# Truss-Power.net
KiCad netlist of a schematic drawn in EAGLE
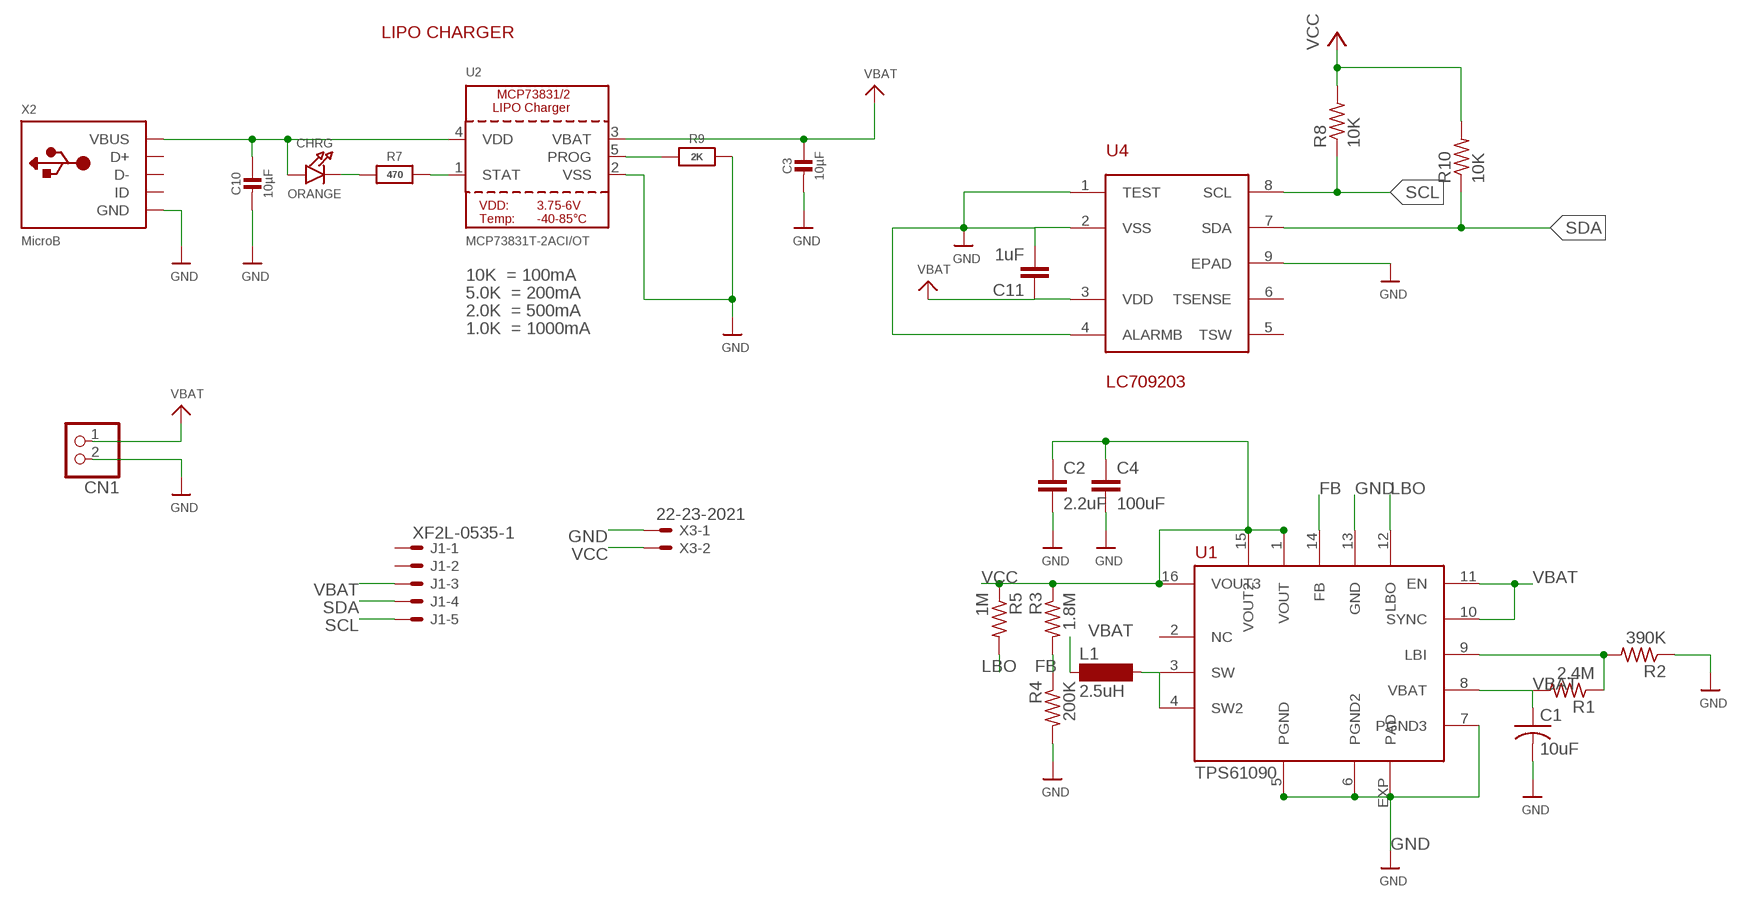
[diagram p0: schematic, sheet 1]

(export (version "E")
  (design (tool "Eeschema 10.0.6"))
  (components
    (comp (ref "C1")
      (value "10uF")
      (footprint "eagle-import:C0805K")
      (libsource (lib "eagle-import") (part "C-USC0805K"))
    )
    (comp (ref "C2")
      (value "2.2uF")
      (footprint "eagle-import:C0805K")
      (libsource (lib "eagle-import") (part "C-EUC0805K"))
    )
    (comp (ref "C3")
      (value "10µF")
      (footprint "eagle-import:0805-NO")
      (libsource (lib "eagle-import") (part "CAP_CERAMIC0805-NOOUTLINE"))
    )
    (comp (ref "C4")
      (value "100uF")
      (footprint "eagle-import:7343-METRIC")
      (libsource (lib "eagle-import") (part "TANT-CAP"))
    )
    (comp (ref "C10")
      (value "10µF")
      (footprint "eagle-import:0805-NO")
      (libsource (lib "eagle-import") (part "CAP_CERAMIC0805-NOOUTLINE"))
    )
    (comp (ref "C11")
      (value "1uF")
      (footprint "eagle-import:C0603")
      (libsource (lib "eagle-import") (part "C-EUC0603"))
    )
    (comp (ref "CHRG")
      (value "ORANGE")
      (footprint "eagle-import:CHIPLED_0805_NOOUTLINE")
      (libsource (lib "eagle-import") (part "LED0805_NOOUTLINE"))
    )
    (comp (ref "CN1")
      (value "JST_2PIN-SMT-RA")
      (footprint "eagle-import:JST-PH-2-SMT-RA")
      (libsource (lib "eagle-import") (part "JST_2PIN-SMT-RA"))
    )
    (comp (ref "J1")
      (value "XF2L-0535-1")
      (footprint "eagle-import:XF2L-0535-1")
      (fields (field (name "MPN") "XF2L-0535-1A"))
      (libsource (lib "eagle-import") (part "XF2-05?35-1L"))
    )
    (comp (ref "L1")
      (value "2.5uH")
      (footprint "eagle-import:CDRH5D28")
      (libsource (lib "eagle-import") (part "CDRH5D28"))
    )
    (comp (ref "R1")
      (value "2.4M")
      (footprint "eagle-import:R0603")
      (libsource (lib "eagle-import") (part "R-US_R0603"))
    )
    (comp (ref "R2")
      (value "390K")
      (footprint "eagle-import:R0603")
      (libsource (lib "eagle-import") (part "R-US_R0603"))
    )
    (comp (ref "R3")
      (value "1.8M")
      (footprint "eagle-import:R0603")
      (libsource (lib "eagle-import") (part "R-US_R0603"))
    )
    (comp (ref "R4")
      (value "200K")
      (footprint "eagle-import:R0603")
      (libsource (lib "eagle-import") (part "R-US_R0603"))
    )
    (comp (ref "R5")
      (value "1M")
      (footprint "eagle-import:R0603")
      (libsource (lib "eagle-import") (part "R-US_R0603"))
    )
    (comp (ref "R7")
      (value "470")
      (footprint "eagle-import:0805-NO")
      (libsource (lib "eagle-import") (part "RESISTOR0805_NOOUTLINE"))
    )
    (comp (ref "R8")
      (value "10K")
      (footprint "eagle-import:R0402")
      (libsource (lib "eagle-import") (part "resistor_R-US_R0402"))
    )
    (comp (ref "R9")
      (value "2K")
      (footprint "eagle-import:0805-NO")
      (libsource (lib "eagle-import") (part "RESISTOR0805_NOOUTLINE"))
    )
    (comp (ref "R10")
      (value "10K")
      (footprint "eagle-import:R0402")
      (libsource (lib "eagle-import") (part "resistor_R-US_R0402"))
    )
    (comp (ref "U1")
      (value "TPS61090")
      (footprint "eagle-import:TPS61090")
      (libsource (lib "eagle-import") (part "TPS61090"))
    )
    (comp (ref "U2")
      (value "MCP73831T-2ACI/OT")
      (footprint "eagle-import:SOT23-5")
      (libsource (lib "eagle-import") (part "MCP73831/2"))
    )
    (comp (ref "U4")
      (value "LC709203")
      (footprint "eagle-import:WDFN8")
      (libsource (lib "eagle-import") (part "LC709203"))
    )
    (comp (ref "X2")
      (value "MicroB")
      (footprint "eagle-import:4UCONN_20329")
      (libsource (lib "eagle-import") (part "USBMICRO_20329"))
    )
    (comp (ref "X3")
      (value "22-23-2021")
      (footprint "eagle-import:22-23-2021")
      (fields (field (name "MF") "MOLEX"))
      (libsource (lib "eagle-import") (part "22-23-2021"))
    )
  )
  (nets
    (net (code "1") (name "/FB") (class "Default")
      (node (ref "R3") (pin "2") (pinfunction "2_2") (pintype "passive"))
      (node (ref "R4") (pin "1") (pinfunction "1_1") (pintype "passive"))
      (node (ref "U1") (pin "14") (pinfunction "FB_14") (pintype "bidirectional"))
    )
    (net (code "2") (name "/LBO") (class "Default")
      (node (ref "R5") (pin "2") (pinfunction "2_2") (pintype "passive"))
      (node (ref "U1") (pin "12") (pinfunction "LBO_12") (pintype "bidirectional"))
    )
    (net (code "3") (name "GND") (class "Default")
      (node (ref "C1") (pin "2") (pinfunction "2_2") (pintype "passive"))
      (node (ref "C10") (pin "2") (pinfunction "2_2") (pintype "passive"))
      (node (ref "C11") (pin "2") (pinfunction "2_2") (pintype "passive"))
      (node (ref "C2") (pin "2") (pinfunction "2_2") (pintype "passive"))
      (node (ref "C3") (pin "2") (pinfunction "2_2") (pintype "passive"))
      (node (ref "C4") (pin "2") (pinfunction "2_2") (pintype "passive"))
      (node (ref "CN1") (pin "2") (pinfunction "1_2") (pintype "passive"))
      (node (ref "R2") (pin "1") (pinfunction "1_1") (pintype "passive"))
      (node (ref "R4") (pin "2") (pinfunction "2_2") (pintype "passive"))
      (node (ref "R9") (pin "2") (pinfunction "2_2") (pintype "passive"))
      (node (ref "U1") (pin "13") (pinfunction "GND_13") (pintype "bidirectional"))
      (node (ref "U1") (pin "5") (pinfunction "PGND_5") (pintype "bidirectional"))
      (node (ref "U1") (pin "6") (pinfunction "PGND2_6") (pintype "bidirectional"))
      (node (ref "U1") (pin "7") (pinfunction "PGND3_7") (pintype "bidirectional"))
      (node (ref "U1") (pin "EXP") (pinfunction "PAD_EXP") (pintype "bidirectional"))
      (node (ref "U2") (pin "2") (pinfunction "VSS_2") (pintype "power_in"))
      (node (ref "U4") (pin "1") (pinfunction "TEST_1") (pintype "bidirectional"))
      (node (ref "U4") (pin "2") (pinfunction "VSS_2") (pintype "bidirectional"))
      (node (ref "U4") (pin "4") (pinfunction "ALARMB_4") (pintype "bidirectional"))
      (node (ref "U4") (pin "9") (pinfunction "EPAD_9") (pintype "bidirectional"))
      (node (ref "X2") (pin "BASE@1") (pinfunction "GND_BASE@1") (pintype "power_in"))
      (node (ref "X2") (pin "BASE@2") (pinfunction "GND_BASE@2") (pintype "power_in"))
      (node (ref "X2") (pin "GND") (pinfunction "GND_GND") (pintype "power_in"))
      (node (ref "X2") (pin "SPRT@1") (pinfunction "GND_SPRT@1") (pintype "power_in"))
      (node (ref "X2") (pin "SPRT@2") (pinfunction "GND_SPRT@2") (pintype "power_in"))
      (node (ref "X2") (pin "SPRT@3") (pinfunction "GND_SPRT@3") (pintype "power_in"))
      (node (ref "X2") (pin "SPRT@4") (pinfunction "GND_SPRT@4") (pintype "power_in"))
      (node (ref "X3") (pin "1") (pinfunction "S_1") (pintype "passive"))
    )
    (net (code "4") (name "Net-(CHRG-PadC)") (class "Default")
      (node (ref "CHRG") (pin "C") (pinfunction "C_C") (pintype "passive"))
      (node (ref "R7") (pin "1") (pinfunction "1_1") (pintype "passive"))
    )
    (net (code "5") (name "Net-(U1-LBI)") (class "Default")
      (node (ref "R1") (pin "1") (pinfunction "1_1") (pintype "passive"))
      (node (ref "R2") (pin "2") (pinfunction "2_2") (pintype "passive"))
      (node (ref "U1") (pin "9") (pinfunction "LBI_9") (pintype "bidirectional"))
    )
    (net (code "6") (name "Net-(U1-SW)") (class "Default")
      (node (ref "L1") (pin "2") (pinfunction "2_2") (pintype "passive"))
      (node (ref "U1") (pin "3") (pinfunction "SW_3") (pintype "bidirectional"))
      (node (ref "U1") (pin "4") (pinfunction "SW2_4") (pintype "bidirectional"))
    )
    (net (code "7") (name "Net-(U2-PROG)") (class "Default")
      (node (ref "R9") (pin "1") (pinfunction "1_1") (pintype "passive"))
      (node (ref "U2") (pin "5") (pinfunction "PROG_5") (pintype "input"))
    )
    (net (code "8") (name "Net-(U2-STAT)") (class "Default")
      (node (ref "R7") (pin "2") (pinfunction "2_2") (pintype "passive"))
      (node (ref "U2") (pin "1") (pinfunction "STAT_1") (pintype "output"))
    )
    (net (code "9") (name "Net-(U2-VDD)") (class "Default")
      (node (ref "C10") (pin "1") (pinfunction "1_1") (pintype "passive"))
      (node (ref "CHRG") (pin "A") (pinfunction "A_A") (pintype "passive"))
      (node (ref "U2") (pin "4") (pinfunction "VDD_4") (pintype "power_in"))
      (node (ref "X2") (pin "VBUS") (pinfunction "VBUS_VBUS") (pintype "power_in"))
    )
    (net (code "10") (name "SCL") (class "Default")
      (node (ref "J1") (pin "5") (pinfunction "MS_5") (pintype "passive"))
      (node (ref "R8") (pin "1") (pinfunction "1_1") (pintype "passive"))
      (node (ref "U4") (pin "8") (pinfunction "SCL_8") (pintype "bidirectional"))
    )
    (net (code "11") (name "SDA") (class "Default")
      (node (ref "J1") (pin "4") (pinfunction "MS_4") (pintype "passive"))
      (node (ref "R10") (pin "1") (pinfunction "1_1") (pintype "passive"))
      (node (ref "U4") (pin "7") (pinfunction "SDA_7") (pintype "bidirectional"))
    )
    (net (code "12") (name "VBAT") (class "Default")
      (node (ref "C1") (pin "1") (pinfunction "1_1") (pintype "passive"))
      (node (ref "C11") (pin "1") (pinfunction "1_1") (pintype "passive"))
      (node (ref "C3") (pin "1") (pinfunction "1_1") (pintype "passive"))
      (node (ref "CN1") (pin "1") (pinfunction "2_1") (pintype "passive"))
      (node (ref "J1") (pin "3") (pinfunction "MS_3") (pintype "passive"))
      (node (ref "L1") (pin "1") (pinfunction "1_1") (pintype "passive"))
      (node (ref "R1") (pin "2") (pinfunction "2_2") (pintype "passive"))
      (node (ref "U1") (pin "10") (pinfunction "SYNC_10") (pintype "bidirectional"))
      (node (ref "U1") (pin "11") (pinfunction "EN_11") (pintype "bidirectional"))
      (node (ref "U1") (pin "8") (pinfunction "VBAT_8") (pintype "bidirectional"))
      (node (ref "U2") (pin "3") (pinfunction "VBAT_3") (pintype "power_in"))
      (node (ref "U4") (pin "3") (pinfunction "VDD_3") (pintype "bidirectional"))
    )
    (net (code "13") (name "VCC") (class "Default")
      (node (ref "C2") (pin "1") (pinfunction "1_1") (pintype "passive"))
      (node (ref "C4") (pin "1") (pinfunction "1_1") (pintype "passive"))
      (node (ref "R10") (pin "2") (pinfunction "2_2") (pintype "passive"))
      (node (ref "R3") (pin "1") (pinfunction "1_1") (pintype "passive"))
      (node (ref "R5") (pin "1") (pinfunction "1_1") (pintype "passive"))
      (node (ref "R8") (pin "2") (pinfunction "2_2") (pintype "passive"))
      (node (ref "U1") (pin "1") (pinfunction "VOUT_1") (pintype "bidirectional"))
      (node (ref "U1") (pin "15") (pinfunction "VOUT2_15") (pintype "bidirectional"))
      (node (ref "U1") (pin "16") (pinfunction "VOUT3_16") (pintype "bidirectional"))
      (node (ref "X3") (pin "2") (pinfunction "S_2") (pintype "passive"))
    )
    (net (code "14") (name "unconnected-(J1A-MSV-Pad1)") (class "Default")
      (node (ref "J1") (pin "1") (pinfunction "MSV_1") (pintype "passive"))
    )
    (net (code "15") (name "unconnected-(J1B-MS-Pad2)") (class "Default")
      (node (ref "J1") (pin "2") (pinfunction "MS_2") (pintype "passive"))
    )
    (net (code "16") (name "unconnected-(U1-NC-Pad2)") (class "Default")
      (node (ref "U1") (pin "2") (pinfunction "NC_2") (pintype "bidirectional"))
    )
    (net (code "17") (name "unconnected-(U4-TSENSE-Pad6)") (class "Default")
      (node (ref "U4") (pin "6") (pinfunction "TSENSE_6") (pintype "bidirectional"))
    )
    (net (code "18") (name "unconnected-(U4-TSW-Pad5)") (class "Default")
      (node (ref "U4") (pin "5") (pinfunction "TSW_5") (pintype "bidirectional"))
    )
    (net (code "19") (name "unconnected-(X2-PadD+)") (class "Default")
      (node (ref "X2") (pin "D+") (pinfunction "D+_D+") (pintype "bidirectional"))
    )
    (net (code "20") (name "unconnected-(X2-PadD-)") (class "Default")
      (node (ref "X2") (pin "D-") (pinfunction "D-_D-") (pintype "bidirectional"))
    )
    (net (code "21") (name "unconnected-(X2-PadID)") (class "Default")
      (node (ref "X2") (pin "ID") (pinfunction "ID_ID") (pintype "bidirectional"))
    )
  )
)
